# BD0005.net
KiCad netlist of a schematic drawn in EAGLE
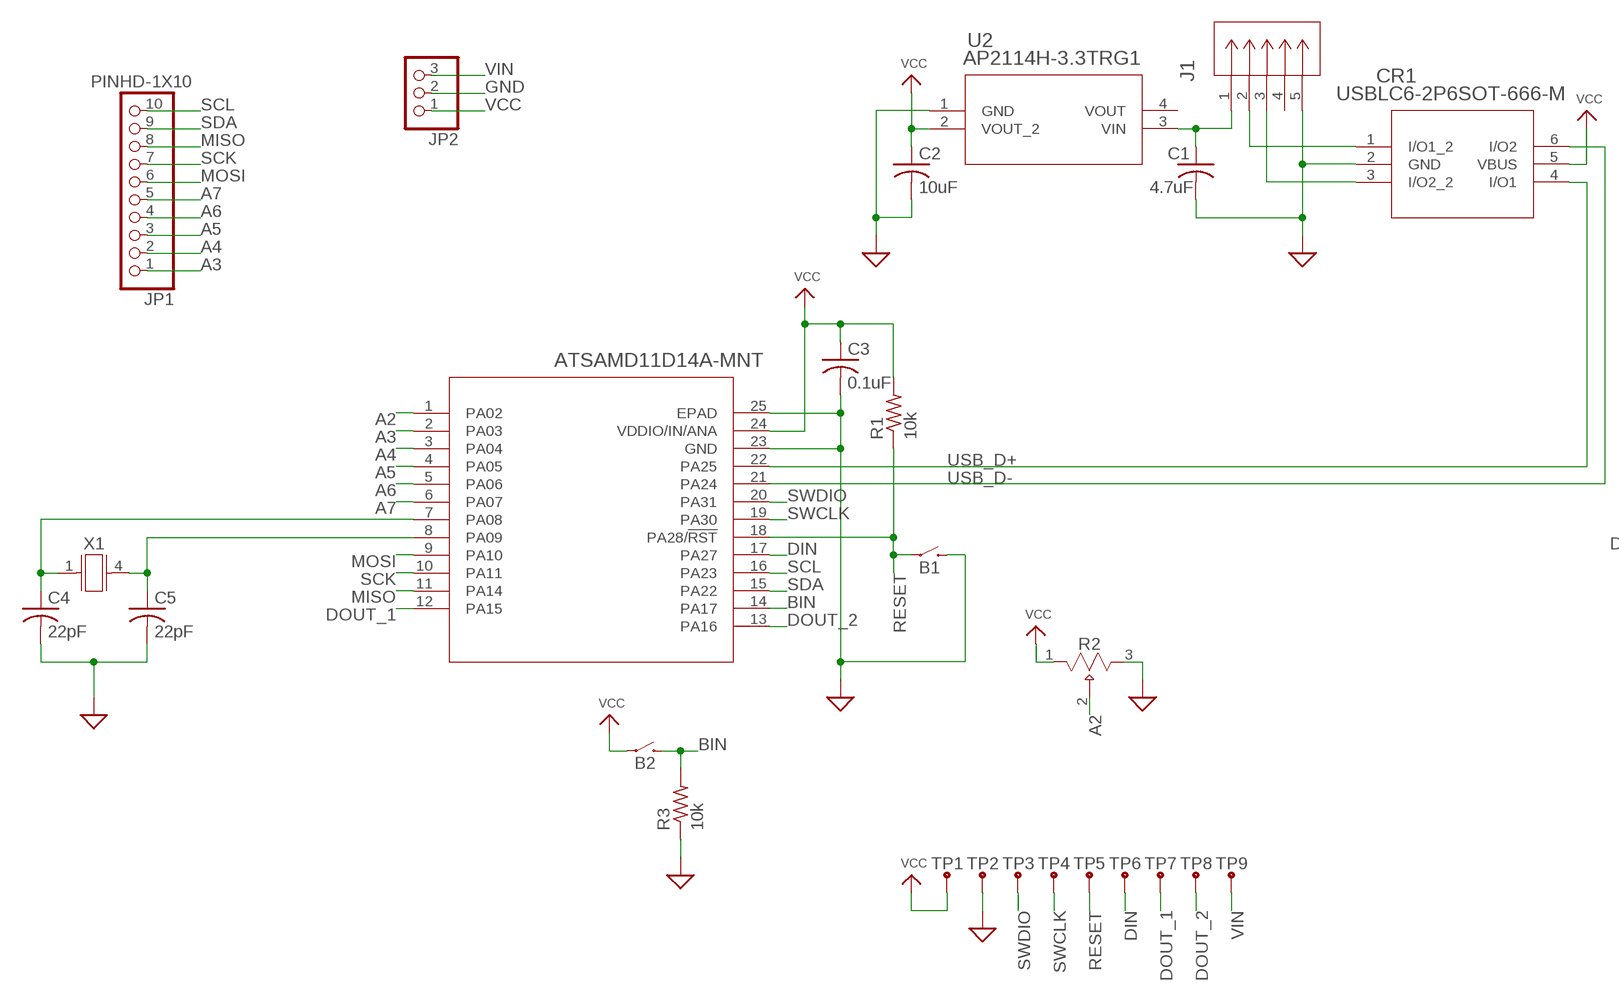
[diagram p0: schematic, sheet 1, part 1 of 2]
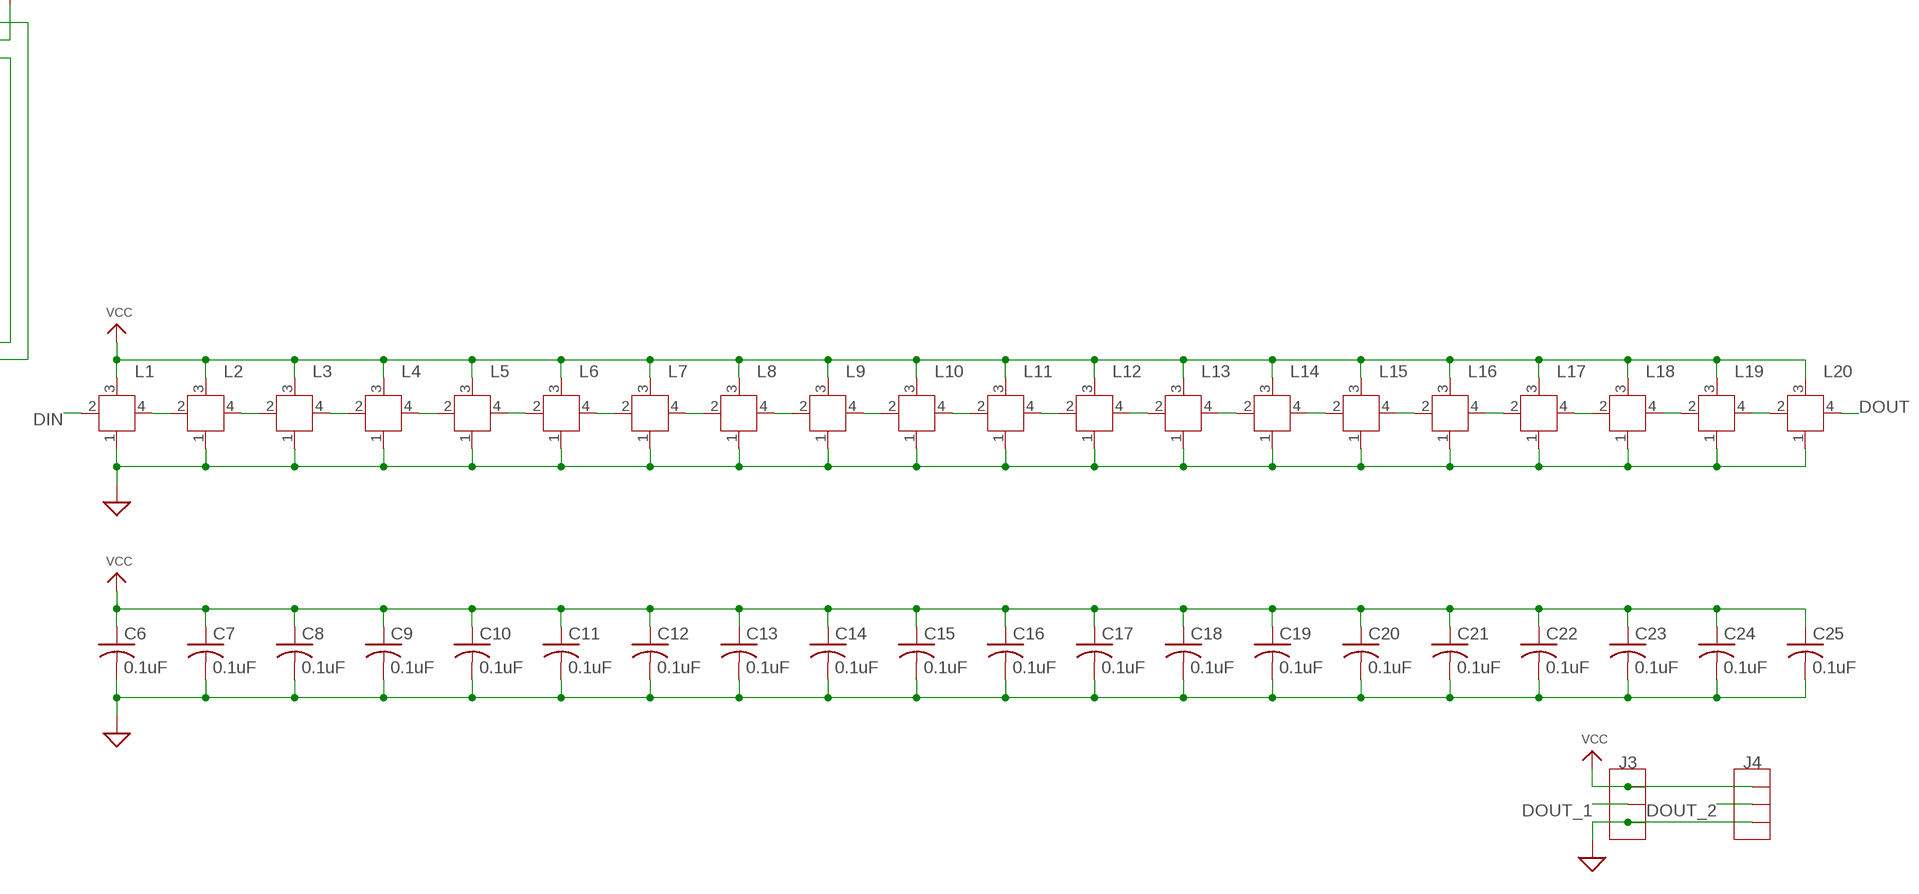
[diagram p1: schematic, sheet 1, part 2 of 2]

(export (version "E")
  (design (tool "Eeschema 10.0.6"))
  (components
    (comp (ref "B1")
      (value "EVQ-P7A01P")
      (footprint "eagle-import:4-SMD_BUTTON")
      (libsource (lib "eagle-import") (part "EVQ-P7A01P"))
    )
    (comp (ref "B2")
      (value "EVQ-P7A01P")
      (footprint "eagle-import:4-SMD_BUTTON")
      (libsource (lib "eagle-import") (part "EVQ-P7A01P"))
    )
    (comp (ref "C1")
      (value "4.7uF")
      (footprint "eagle-import:C0805")
      (libsource (lib "eagle-import") (part "C-USC0805"))
    )
    (comp (ref "C2")
      (value "10uF")
      (footprint "eagle-import:C0805")
      (libsource (lib "eagle-import") (part "C-USC0805"))
    )
    (comp (ref "C3")
      (value "0.1uF")
      (footprint "eagle-import:C0402")
      (libsource (lib "eagle-import") (part "C-USC0402"))
    )
    (comp (ref "C4")
      (value "22pF")
      (footprint "eagle-import:C0402")
      (libsource (lib "eagle-import") (part "C-USC0402"))
    )
    (comp (ref "C5")
      (value "22pF")
      (footprint "eagle-import:C0402")
      (libsource (lib "eagle-import") (part "C-USC0402"))
    )
    (comp (ref "C6")
      (value "0.1uF")
      (footprint "eagle-import:C0402")
      (libsource (lib "eagle-import") (part "C-USC0402"))
    )
    (comp (ref "C7")
      (value "0.1uF")
      (footprint "eagle-import:C0402")
      (libsource (lib "eagle-import") (part "C-USC0402"))
    )
    (comp (ref "C8")
      (value "0.1uF")
      (footprint "eagle-import:C0402")
      (libsource (lib "eagle-import") (part "C-USC0402"))
    )
    (comp (ref "C9")
      (value "0.1uF")
      (footprint "eagle-import:C0402")
      (libsource (lib "eagle-import") (part "C-USC0402"))
    )
    (comp (ref "C10")
      (value "0.1uF")
      (footprint "eagle-import:C0402")
      (libsource (lib "eagle-import") (part "C-USC0402"))
    )
    (comp (ref "C11")
      (value "0.1uF")
      (footprint "eagle-import:C0402")
      (libsource (lib "eagle-import") (part "C-USC0402"))
    )
    (comp (ref "C12")
      (value "0.1uF")
      (footprint "eagle-import:C0402")
      (libsource (lib "eagle-import") (part "C-USC0402"))
    )
    (comp (ref "C13")
      (value "0.1uF")
      (footprint "eagle-import:C0402")
      (libsource (lib "eagle-import") (part "C-USC0402"))
    )
    (comp (ref "C14")
      (value "0.1uF")
      (footprint "eagle-import:C0402")
      (libsource (lib "eagle-import") (part "C-USC0402"))
    )
    (comp (ref "C15")
      (value "0.1uF")
      (footprint "eagle-import:C0402")
      (libsource (lib "eagle-import") (part "C-USC0402"))
    )
    (comp (ref "C16")
      (value "0.1uF")
      (footprint "eagle-import:C0402")
      (libsource (lib "eagle-import") (part "C-USC0402"))
    )
    (comp (ref "C17")
      (value "0.1uF")
      (footprint "eagle-import:C0402")
      (libsource (lib "eagle-import") (part "C-USC0402"))
    )
    (comp (ref "C18")
      (value "0.1uF")
      (footprint "eagle-import:C0402")
      (libsource (lib "eagle-import") (part "C-USC0402"))
    )
    (comp (ref "C19")
      (value "0.1uF")
      (footprint "eagle-import:C0402")
      (libsource (lib "eagle-import") (part "C-USC0402"))
    )
    (comp (ref "C20")
      (value "0.1uF")
      (footprint "eagle-import:C0402")
      (libsource (lib "eagle-import") (part "C-USC0402"))
    )
    (comp (ref "C21")
      (value "0.1uF")
      (footprint "eagle-import:C0402")
      (libsource (lib "eagle-import") (part "C-USC0402"))
    )
    (comp (ref "C22")
      (value "0.1uF")
      (footprint "eagle-import:C0402")
      (libsource (lib "eagle-import") (part "C-USC0402"))
    )
    (comp (ref "C23")
      (value "0.1uF")
      (footprint "eagle-import:C0402")
      (libsource (lib "eagle-import") (part "C-USC0402"))
    )
    (comp (ref "C24")
      (value "0.1uF")
      (footprint "eagle-import:C0402")
      (libsource (lib "eagle-import") (part "C-USC0402"))
    )
    (comp (ref "C25")
      (value "0.1uF")
      (footprint "eagle-import:C0402")
      (libsource (lib "eagle-import") (part "C-USC0402"))
    )
    (comp (ref "CR1")
      (value "USBLC6-2P6SOT-666-M")
      (footprint "eagle-import:SOT-666-M")
      (fields (field (name "MANUFACTURER_PART_NUMBER") "USBLC6-2P6"))
      (libsource (lib "eagle-import") (part "USBLC6-2P6SOT-666-M"))
    )
    (comp (ref "J1")
      (value "1050171001")
      (footprint "eagle-import:CON00679_5")
      (fields (field (name "COPYRIGHT") "Copyright (C) 2016 Accelerated Designs. All rights reserved"))
      (libsource (lib "eagle-import") (part "1050171001"))
    )
    (comp (ref "J3")
      (value "HEADER_1X3FEMALE")
      (footprint "eagle-import:F3SMD")
      (libsource (lib "eagle-import") (part "HEADER_1X3FEMALE"))
    )
    (comp (ref "J4")
      (value "HEADER_1X3FEMALE")
      (footprint "eagle-import:F3SMD")
      (libsource (lib "eagle-import") (part "HEADER_1X3FEMALE"))
    )
    (comp (ref "JP1")
      (value "PINHD-1X10")
      (footprint "eagle-import:1X10-BIG")
      (libsource (lib "eagle-import") (part "PINHD-1X10"))
    )
    (comp (ref "JP2")
      (value "PINHD-1X3")
      (footprint "eagle-import:1X03")
      (libsource (lib "eagle-import") (part "PINHD-1X3"))
    )
    (comp (ref "L1")
      (value "WS2812B")
      (footprint "eagle-import:SK6812")
      (libsource (lib "eagle-import") (part "WS2812B"))
    )
    (comp (ref "L2")
      (value "WS2812B")
      (footprint "eagle-import:SK6812")
      (libsource (lib "eagle-import") (part "WS2812B"))
    )
    (comp (ref "L3")
      (value "WS2812B")
      (footprint "eagle-import:SK6812")
      (libsource (lib "eagle-import") (part "WS2812B"))
    )
    (comp (ref "L4")
      (value "WS2812B")
      (footprint "eagle-import:SK6812")
      (libsource (lib "eagle-import") (part "WS2812B"))
    )
    (comp (ref "L5")
      (value "WS2812B")
      (footprint "eagle-import:SK6812")
      (libsource (lib "eagle-import") (part "WS2812B"))
    )
    (comp (ref "L6")
      (value "WS2812B")
      (footprint "eagle-import:SK6812")
      (libsource (lib "eagle-import") (part "WS2812B"))
    )
    (comp (ref "L7")
      (value "WS2812B")
      (footprint "eagle-import:SK6812")
      (libsource (lib "eagle-import") (part "WS2812B"))
    )
    (comp (ref "L8")
      (value "WS2812B")
      (footprint "eagle-import:SK6812")
      (libsource (lib "eagle-import") (part "WS2812B"))
    )
    (comp (ref "L9")
      (value "WS2812B")
      (footprint "eagle-import:SK6812")
      (libsource (lib "eagle-import") (part "WS2812B"))
    )
    (comp (ref "L10")
      (value "WS2812B")
      (footprint "eagle-import:SK6812")
      (libsource (lib "eagle-import") (part "WS2812B"))
    )
    (comp (ref "L11")
      (value "WS2812B")
      (footprint "eagle-import:SK6812")
      (libsource (lib "eagle-import") (part "WS2812B"))
    )
    (comp (ref "L12")
      (value "WS2812B")
      (footprint "eagle-import:SK6812")
      (libsource (lib "eagle-import") (part "WS2812B"))
    )
    (comp (ref "L13")
      (value "WS2812B")
      (footprint "eagle-import:SK6812")
      (libsource (lib "eagle-import") (part "WS2812B"))
    )
    (comp (ref "L14")
      (value "WS2812B")
      (footprint "eagle-import:SK6812")
      (libsource (lib "eagle-import") (part "WS2812B"))
    )
    (comp (ref "L15")
      (value "WS2812B")
      (footprint "eagle-import:SK6812")
      (libsource (lib "eagle-import") (part "WS2812B"))
    )
    (comp (ref "L16")
      (value "WS2812B")
      (footprint "eagle-import:SK6812")
      (libsource (lib "eagle-import") (part "WS2812B"))
    )
    (comp (ref "L17")
      (value "WS2812B")
      (footprint "eagle-import:SK6812")
      (libsource (lib "eagle-import") (part "WS2812B"))
    )
    (comp (ref "L18")
      (value "WS2812B")
      (footprint "eagle-import:SK6812")
      (libsource (lib "eagle-import") (part "WS2812B"))
    )
    (comp (ref "L19")
      (value "WS2812B")
      (footprint "eagle-import:SK6812")
      (libsource (lib "eagle-import") (part "WS2812B"))
    )
    (comp (ref "L20")
      (value "WS2812B")
      (footprint "eagle-import:SK6812")
      (libsource (lib "eagle-import") (part "WS2812B"))
    )
    (comp (ref "R1")
      (value "10k")
      (footprint "eagle-import:R0402")
      (libsource (lib "eagle-import") (part "R-US_R0402"))
    )
    (comp (ref "R2")
      (value "3352T-1-104LF")
      (footprint "eagle-import:THUMBWHEEL")
      (libsource (lib "eagle-import") (part "3352T-1-104LF"))
    )
    (comp (ref "R3")
      (value "10k")
      (footprint "eagle-import:R0402")
      (libsource (lib "eagle-import") (part "R-US_R0402"))
    )
    (comp (ref "TP1")
      (value "VCC")
      (footprint "eagle-import:TEST_POINT")
      (libsource (lib "eagle-import") (part "TEST_POINT"))
    )
    (comp (ref "TP2")
      (value "GND")
      (footprint "eagle-import:TEST_POINT")
      (libsource (lib "eagle-import") (part "TEST_POINT"))
    )
    (comp (ref "TP3")
      (value "DIO")
      (footprint "eagle-import:TEST_POINT")
      (libsource (lib "eagle-import") (part "TEST_POINT"))
    )
    (comp (ref "TP4")
      (value "CLK")
      (footprint "eagle-import:TEST_POINT")
      (libsource (lib "eagle-import") (part "TEST_POINT"))
    )
    (comp (ref "TP5")
      (value "RST")
      (footprint "eagle-import:TEST_POINT")
      (libsource (lib "eagle-import") (part "TEST_POINT"))
    )
    (comp (ref "TP6")
      (value "DIN")
      (footprint "eagle-import:TEST_POINT")
      (libsource (lib "eagle-import") (part "TEST_POINT"))
    )
    (comp (ref "TP7")
      (value "DO1")
      (footprint "eagle-import:TEST_POINT")
      (libsource (lib "eagle-import") (part "TEST_POINT"))
    )
    (comp (ref "TP8")
      (value "DO2")
      (footprint "eagle-import:TEST_POINT")
      (libsource (lib "eagle-import") (part "TEST_POINT"))
    )
    (comp (ref "TP9")
      (value "VIN")
      (footprint "eagle-import:TEST_POINT")
      (libsource (lib "eagle-import") (part "TEST_POINT"))
    )
    (comp (ref "U1")
      (value "ATSAMD11D14A-MNT")
      (footprint "eagle-import:QFN24_4X4MC")
      (fields (field (name "COPYRIGHT") "Copyright (C) 2018 Accelerated Designs. All rights reserved"))
      (libsource (lib "eagle-import") (part "ATSAMD11D14A-MNT"))
    )
    (comp (ref "U2")
      (value "AP2114H-3.3TRG1")
      (footprint "eagle-import:SOT-223")
      (libsource (lib "eagle-import") (part "AP2114H-3.3TRG1"))
    )
    (comp (ref "X1")
      (value "MC-146-32.7680JKA-A0:ROHS")
      (footprint "eagle-import:4-SMD_FLAT_LEADS")
      (libsource (lib "eagle-import") (part "MC-146-32.7680JKA-A0{colon}ROHS"))
    )
  )
  (nets
    (net (code "1") (name "/A2") (class "Default")
      (node (ref "R2") (pin "2") (pinfunction "P$2_2") (pintype "bidirectional"))
      (node (ref "U1") (pin "1") (pinfunction "PA02_1") (pintype "bidirectional"))
    )
    (net (code "2") (name "/A3") (class "Default")
      (node (ref "JP1") (pin "1") (pinfunction "1_1") (pintype "passive"))
      (node (ref "U1") (pin "2") (pinfunction "PA03_2") (pintype "bidirectional"))
    )
    (net (code "3") (name "/A4") (class "Default")
      (node (ref "JP1") (pin "2") (pinfunction "2_2") (pintype "passive"))
      (node (ref "U1") (pin "3") (pinfunction "PA04_3") (pintype "bidirectional"))
    )
    (net (code "4") (name "/A5") (class "Default")
      (node (ref "JP1") (pin "3") (pinfunction "3_3") (pintype "passive"))
      (node (ref "U1") (pin "4") (pinfunction "PA05_4") (pintype "bidirectional"))
    )
    (net (code "5") (name "/A6") (class "Default")
      (node (ref "JP1") (pin "4") (pinfunction "4_4") (pintype "passive"))
      (node (ref "U1") (pin "5") (pinfunction "PA06_5") (pintype "bidirectional"))
    )
    (net (code "6") (name "/A7") (class "Default")
      (node (ref "JP1") (pin "5") (pinfunction "5_5") (pintype "passive"))
      (node (ref "U1") (pin "6") (pinfunction "PA07_6") (pintype "bidirectional"))
    )
    (net (code "7") (name "/BIN") (class "Default")
      (node (ref "B2") (pin "2A") (pinfunction "P$2_2A") (pintype "bidirectional"))
      (node (ref "B2") (pin "2B") (pinfunction "P$2_2B") (pintype "bidirectional"))
      (node (ref "R3") (pin "2") (pinfunction "2_2") (pintype "passive"))
      (node (ref "U1") (pin "14") (pinfunction "PA17_14") (pintype "bidirectional"))
    )
    (net (code "8") (name "/DIN") (class "Default")
      (node (ref "L1") (pin "2") (pinfunction "DIN_2") (pintype "bidirectional"))
      (node (ref "TP6") (pin "P$1") (pinfunction "P$1_P$1") (pintype "input"))
      (node (ref "U1") (pin "17") (pinfunction "PA27_17") (pintype "bidirectional"))
    )
    (net (code "9") (name "/DOUT") (class "Default")
      (node (ref "L20") (pin "4") (pinfunction "DOUT_4") (pintype "bidirectional"))
    )
    (net (code "10") (name "/DOUT_1") (class "Default")
      (node (ref "J3") (pin "2A") (pinfunction "P$2_2A") (pintype "bidirectional"))
      (node (ref "J3") (pin "2B") (pinfunction "P$2_2B") (pintype "bidirectional"))
      (node (ref "TP7") (pin "P$1") (pinfunction "P$1_P$1") (pintype "input"))
      (node (ref "U1") (pin "12") (pinfunction "PA15_12") (pintype "bidirectional"))
    )
    (net (code "11") (name "/DOUT_2") (class "Default")
      (node (ref "J4") (pin "2A") (pinfunction "P$2_2A") (pintype "bidirectional"))
      (node (ref "J4") (pin "2B") (pinfunction "P$2_2B") (pintype "bidirectional"))
      (node (ref "TP8") (pin "P$1") (pinfunction "P$1_P$1") (pintype "input"))
      (node (ref "U1") (pin "13") (pinfunction "PA16_13") (pintype "bidirectional"))
    )
    (net (code "12") (name "/MISO") (class "Default")
      (node (ref "JP1") (pin "8") (pinfunction "8_8") (pintype "passive"))
      (node (ref "U1") (pin "11") (pinfunction "PA14_11") (pintype "bidirectional"))
    )
    (net (code "13") (name "/MOSI") (class "Default")
      (node (ref "JP1") (pin "6") (pinfunction "6_6") (pintype "passive"))
      (node (ref "U1") (pin "9") (pinfunction "PA10_9") (pintype "bidirectional"))
    )
    (net (code "14") (name "/RESET") (class "Default")
      (node (ref "B1") (pin "1A") (pinfunction "P$1_1A") (pintype "bidirectional"))
      (node (ref "B1") (pin "1B") (pinfunction "P$1_1B") (pintype "bidirectional"))
      (node (ref "R1") (pin "1") (pinfunction "1_1") (pintype "passive"))
      (node (ref "TP5") (pin "P$1") (pinfunction "P$1_P$1") (pintype "input"))
      (node (ref "U1") (pin "18") (pinfunction "PA28/~{RST}_18") (pintype "bidirectional"))
    )
    (net (code "15") (name "/SCK") (class "Default")
      (node (ref "JP1") (pin "7") (pinfunction "7_7") (pintype "passive"))
      (node (ref "U1") (pin "10") (pinfunction "PA11_10") (pintype "bidirectional"))
    )
    (net (code "16") (name "/SCL") (class "Default")
      (node (ref "JP1") (pin "10") (pinfunction "10_10") (pintype "passive"))
      (node (ref "U1") (pin "16") (pinfunction "PA23_16") (pintype "bidirectional"))
    )
    (net (code "17") (name "/SDA") (class "Default")
      (node (ref "JP1") (pin "9") (pinfunction "9_9") (pintype "passive"))
      (node (ref "U1") (pin "15") (pinfunction "PA22_15") (pintype "bidirectional"))
    )
    (net (code "18") (name "/SWCLK") (class "Default")
      (node (ref "TP4") (pin "P$1") (pinfunction "P$1_P$1") (pintype "input"))
      (node (ref "U1") (pin "19") (pinfunction "PA30_19") (pintype "bidirectional"))
    )
    (net (code "19") (name "/SWDIO") (class "Default")
      (node (ref "TP3") (pin "P$1") (pinfunction "P$1_P$1") (pintype "input"))
      (node (ref "U1") (pin "20") (pinfunction "PA31_20") (pintype "bidirectional"))
    )
    (net (code "20") (name "/USB_D+") (class "Default")
      (node (ref "CR1") (pin "4") (pinfunction "I/O1_4") (pintype "bidirectional"))
      (node (ref "U1") (pin "22") (pinfunction "PA25_22") (pintype "bidirectional"))
    )
    (net (code "21") (name "/USB_D-") (class "Default")
      (node (ref "CR1") (pin "6") (pinfunction "I/O2_6") (pintype "bidirectional"))
      (node (ref "U1") (pin "21") (pinfunction "PA24_21") (pintype "bidirectional"))
    )
    (net (code "22") (name "/VIN") (class "Default")
      (node (ref "C1") (pin "1") (pinfunction "1_1") (pintype "passive"))
      (node (ref "J1") (pin "1") (pinfunction "1_1") (pintype "passive"))
      (node (ref "JP2") (pin "3") (pinfunction "3_3") (pintype "passive"))
      (node (ref "TP9") (pin "P$1") (pinfunction "P$1_P$1") (pintype "input"))
      (node (ref "U2") (pin "3") (pinfunction "VIN_3") (pintype "input"))
    )
    (net (code "23") (name "Net-(CR1-I{slash}O1_2)") (class "Default")
      (node (ref "CR1") (pin "1") (pinfunction "I/O1_2_1") (pintype "bidirectional"))
      (node (ref "J1") (pin "2") (pinfunction "2_2") (pintype "passive"))
    )
    (net (code "24") (name "Net-(CR1-I{slash}O2_2)") (class "Default")
      (node (ref "CR1") (pin "3") (pinfunction "I/O2_2_3") (pintype "bidirectional"))
      (node (ref "J1") (pin "3") (pinfunction "3_3") (pintype "passive"))
    )
    (net (code "25") (name "Net-(L1-DOUT)") (class "Default")
      (node (ref "L1") (pin "4") (pinfunction "DOUT_4") (pintype "bidirectional"))
      (node (ref "L2") (pin "2") (pinfunction "DIN_2") (pintype "bidirectional"))
    )
    (net (code "26") (name "Net-(L2-DOUT)") (class "Default")
      (node (ref "L2") (pin "4") (pinfunction "DOUT_4") (pintype "bidirectional"))
      (node (ref "L3") (pin "2") (pinfunction "DIN_2") (pintype "bidirectional"))
    )
    (net (code "27") (name "Net-(L3-DOUT)") (class "Default")
      (node (ref "L3") (pin "4") (pinfunction "DOUT_4") (pintype "bidirectional"))
      (node (ref "L4") (pin "2") (pinfunction "DIN_2") (pintype "bidirectional"))
    )
    (net (code "28") (name "Net-(L4-DOUT)") (class "Default")
      (node (ref "L4") (pin "4") (pinfunction "DOUT_4") (pintype "bidirectional"))
      (node (ref "L5") (pin "2") (pinfunction "DIN_2") (pintype "bidirectional"))
    )
    (net (code "29") (name "Net-(L5-DOUT)") (class "Default")
      (node (ref "L5") (pin "4") (pinfunction "DOUT_4") (pintype "bidirectional"))
      (node (ref "L6") (pin "2") (pinfunction "DIN_2") (pintype "bidirectional"))
    )
    (net (code "30") (name "Net-(L6-DOUT)") (class "Default")
      (node (ref "L6") (pin "4") (pinfunction "DOUT_4") (pintype "bidirectional"))
      (node (ref "L7") (pin "2") (pinfunction "DIN_2") (pintype "bidirectional"))
    )
    (net (code "31") (name "Net-(L7-DOUT)") (class "Default")
      (node (ref "L7") (pin "4") (pinfunction "DOUT_4") (pintype "bidirectional"))
      (node (ref "L8") (pin "2") (pinfunction "DIN_2") (pintype "bidirectional"))
    )
    (net (code "32") (name "Net-(L8-DOUT)") (class "Default")
      (node (ref "L8") (pin "4") (pinfunction "DOUT_4") (pintype "bidirectional"))
      (node (ref "L9") (pin "2") (pinfunction "DIN_2") (pintype "bidirectional"))
    )
    (net (code "33") (name "Net-(L10-DIN)") (class "Default")
      (node (ref "L10") (pin "2") (pinfunction "DIN_2") (pintype "bidirectional"))
      (node (ref "L9") (pin "4") (pinfunction "DOUT_4") (pintype "bidirectional"))
    )
    (net (code "34") (name "Net-(L10-DOUT)") (class "Default")
      (node (ref "L10") (pin "4") (pinfunction "DOUT_4") (pintype "bidirectional"))
      (node (ref "L11") (pin "2") (pinfunction "DIN_2") (pintype "bidirectional"))
    )
    (net (code "35") (name "Net-(L11-DOUT)") (class "Default")
      (node (ref "L11") (pin "4") (pinfunction "DOUT_4") (pintype "bidirectional"))
      (node (ref "L12") (pin "2") (pinfunction "DIN_2") (pintype "bidirectional"))
    )
    (net (code "36") (name "Net-(L12-DOUT)") (class "Default")
      (node (ref "L12") (pin "4") (pinfunction "DOUT_4") (pintype "bidirectional"))
      (node (ref "L13") (pin "2") (pinfunction "DIN_2") (pintype "bidirectional"))
    )
    (net (code "37") (name "Net-(L13-DOUT)") (class "Default")
      (node (ref "L13") (pin "4") (pinfunction "DOUT_4") (pintype "bidirectional"))
      (node (ref "L14") (pin "2") (pinfunction "DIN_2") (pintype "bidirectional"))
    )
    (net (code "38") (name "Net-(L14-DOUT)") (class "Default")
      (node (ref "L14") (pin "4") (pinfunction "DOUT_4") (pintype "bidirectional"))
      (node (ref "L15") (pin "2") (pinfunction "DIN_2") (pintype "bidirectional"))
    )
    (net (code "39") (name "Net-(L15-DOUT)") (class "Default")
      (node (ref "L15") (pin "4") (pinfunction "DOUT_4") (pintype "bidirectional"))
      (node (ref "L16") (pin "2") (pinfunction "DIN_2") (pintype "bidirectional"))
    )
    (net (code "40") (name "Net-(L16-DOUT)") (class "Default")
      (node (ref "L16") (pin "4") (pinfunction "DOUT_4") (pintype "bidirectional"))
      (node (ref "L17") (pin "2") (pinfunction "DIN_2") (pintype "bidirectional"))
    )
    (net (code "41") (name "Net-(L17-DOUT)") (class "Default")
      (node (ref "L17") (pin "4") (pinfunction "DOUT_4") (pintype "bidirectional"))
      (node (ref "L18") (pin "2") (pinfunction "DIN_2") (pintype "bidirectional"))
    )
    (net (code "42") (name "Net-(L18-DOUT)") (class "Default")
      (node (ref "L18") (pin "4") (pinfunction "DOUT_4") (pintype "bidirectional"))
      (node (ref "L19") (pin "2") (pinfunction "DIN_2") (pintype "bidirectional"))
    )
    (net (code "43") (name "Net-(L19-DOUT)") (class "Default")
      (node (ref "L19") (pin "4") (pinfunction "DOUT_4") (pintype "bidirectional"))
      (node (ref "L20") (pin "2") (pinfunction "DIN_2") (pintype "bidirectional"))
    )
    (net (code "44") (name "Net-(U1-PA08)") (class "Default")
      (node (ref "C4") (pin "1") (pinfunction "1_1") (pintype "passive"))
      (node (ref "U1") (pin "7") (pinfunction "PA08_7") (pintype "bidirectional"))
      (node (ref "X1") (pin "1") (pinfunction "P$1_1") (pintype "bidirectional"))
    )
    (net (code "45") (name "Net-(U1-PA09)") (class "Default")
      (node (ref "C5") (pin "1") (pinfunction "1_1") (pintype "passive"))
      (node (ref "U1") (pin "8") (pinfunction "PA09_8") (pintype "bidirectional"))
      (node (ref "X1") (pin "4") (pinfunction "P$2_4") (pintype "bidirectional"))
    )
    (net (code "46") (name "SUP") (class "Default")
      (node (ref "B1") (pin "2A") (pinfunction "P$2_2A") (pintype "bidirectional"))
      (node (ref "B1") (pin "2B") (pinfunction "P$2_2B") (pintype "bidirectional"))
      (node (ref "C1") (pin "2") (pinfunction "2_2") (pintype "passive"))
      (node (ref "C10") (pin "2") (pinfunction "2_2") (pintype "passive"))
      (node (ref "C11") (pin "2") (pinfunction "2_2") (pintype "passive"))
      (node (ref "C12") (pin "2") (pinfunction "2_2") (pintype "passive"))
      (node (ref "C13") (pin "2") (pinfunction "2_2") (pintype "passive"))
      (node (ref "C14") (pin "2") (pinfunction "2_2") (pintype "passive"))
      (node (ref "C15") (pin "2") (pinfunction "2_2") (pintype "passive"))
      (node (ref "C16") (pin "2") (pinfunction "2_2") (pintype "passive"))
      (node (ref "C17") (pin "2") (pinfunction "2_2") (pintype "passive"))
      (node (ref "C18") (pin "2") (pinfunction "2_2") (pintype "passive"))
      (node (ref "C19") (pin "2") (pinfunction "2_2") (pintype "passive"))
      (node (ref "C2") (pin "2") (pinfunction "2_2") (pintype "passive"))
      (node (ref "C20") (pin "2") (pinfunction "2_2") (pintype "passive"))
      (node (ref "C21") (pin "2") (pinfunction "2_2") (pintype "passive"))
      (node (ref "C22") (pin "2") (pinfunction "2_2") (pintype "passive"))
      (node (ref "C23") (pin "2") (pinfunction "2_2") (pintype "passive"))
      (node (ref "C24") (pin "2") (pinfunction "2_2") (pintype "passive"))
      (node (ref "C25") (pin "2") (pinfunction "2_2") (pintype "passive"))
      (node (ref "C3") (pin "2") (pinfunction "2_2") (pintype "passive"))
      (node (ref "C4") (pin "2") (pinfunction "2_2") (pintype "passive"))
      (node (ref "C5") (pin "2") (pinfunction "2_2") (pintype "passive"))
      (node (ref "C6") (pin "2") (pinfunction "2_2") (pintype "passive"))
      (node (ref "C7") (pin "2") (pinfunction "2_2") (pintype "passive"))
      (node (ref "C8") (pin "2") (pinfunction "2_2") (pintype "passive"))
      (node (ref "C9") (pin "2") (pinfunction "2_2") (pintype "passive"))
      (node (ref "CR1") (pin "2") (pinfunction "GND_2") (pintype "power_in"))
      (node (ref "J1") (pin "5") (pinfunction "5_5") (pintype "passive"))
      (node (ref "J3") (pin "3A") (pinfunction "P$3_3A") (pintype "bidirectional"))
      (node (ref "J3") (pin "3B") (pinfunction "P$3_3B") (pintype "bidirectional"))
      (node (ref "J4") (pin "3A") (pinfunction "P$3_3A") (pintype "bidirectional"))
      (node (ref "J4") (pin "3B") (pinfunction "P$3_3B") (pintype "bidirectional"))
      (node (ref "JP2") (pin "2") (pinfunction "2_2") (pintype "passive"))
      (node (ref "L1") (pin "1") (pinfunction "VSS_1") (pintype "bidirectional"))
      (node (ref "L10") (pin "1") (pinfunction "VSS_1") (pintype "bidirectional"))
      (node (ref "L11") (pin "1") (pinfunction "VSS_1") (pintype "bidirectional"))
      (node (ref "L12") (pin "1") (pinfunction "VSS_1") (pintype "bidirectional"))
      (node (ref "L13") (pin "1") (pinfunction "VSS_1") (pintype "bidirectional"))
      (node (ref "L14") (pin "1") (pinfunction "VSS_1") (pintype "bidirectional"))
      (node (ref "L15") (pin "1") (pinfunction "VSS_1") (pintype "bidirectional"))
      (node (ref "L16") (pin "1") (pinfunction "VSS_1") (pintype "bidirectional"))
      (node (ref "L17") (pin "1") (pinfunction "VSS_1") (pintype "bidirectional"))
      (node (ref "L18") (pin "1") (pinfunction "VSS_1") (pintype "bidirectional"))
      (node (ref "L19") (pin "1") (pinfunction "VSS_1") (pintype "bidirectional"))
      (node (ref "L2") (pin "1") (pinfunction "VSS_1") (pintype "bidirectional"))
      (node (ref "L20") (pin "1") (pinfunction "VSS_1") (pintype "bidirectional"))
      (node (ref "L3") (pin "1") (pinfunction "VSS_1") (pintype "bidirectional"))
      (node (ref "L4") (pin "1") (pinfunction "VSS_1") (pintype "bidirectional"))
      (node (ref "L5") (pin "1") (pinfunction "VSS_1") (pintype "bidirectional"))
      (node (ref "L6") (pin "1") (pinfunction "VSS_1") (pintype "bidirectional"))
      (node (ref "L7") (pin "1") (pinfunction "VSS_1") (pintype "bidirectional"))
      (node (ref "L8") (pin "1") (pinfunction "VSS_1") (pintype "bidirectional"))
      (node (ref "L9") (pin "1") (pinfunction "VSS_1") (pintype "bidirectional"))
      (node (ref "R2") (pin "3") (pinfunction "P$3_3") (pintype "bidirectional"))
      (node (ref "R3") (pin "1") (pinfunction "1_1") (pintype "passive"))
      (node (ref "TP2") (pin "P$1") (pinfunction "P$1_P$1") (pintype "input"))
      (node (ref "U1") (pin "23") (pinfunction "GND_23") (pintype "passive"))
      (node (ref "U1") (pin "25") (pinfunction "EPAD_25") (pintype "passive"))
      (node (ref "U2") (pin "1") (pinfunction "GND_1") (pintype "passive"))
    )
    (net (code "47") (name "VCC") (class "Default")
      (node (ref "B2") (pin "1A") (pinfunction "P$1_1A") (pintype "bidirectional"))
      (node (ref "B2") (pin "1B") (pinfunction "P$1_1B") (pintype "bidirectional"))
      (node (ref "C10") (pin "1") (pinfunction "1_1") (pintype "passive"))
      (node (ref "C11") (pin "1") (pinfunction "1_1") (pintype "passive"))
      (node (ref "C12") (pin "1") (pinfunction "1_1") (pintype "passive"))
      (node (ref "C13") (pin "1") (pinfunction "1_1") (pintype "passive"))
      (node (ref "C14") (pin "1") (pinfunction "1_1") (pintype "passive"))
      (node (ref "C15") (pin "1") (pinfunction "1_1") (pintype "passive"))
      (node (ref "C16") (pin "1") (pinfunction "1_1") (pintype "passive"))
      (node (ref "C17") (pin "1") (pinfunction "1_1") (pintype "passive"))
      (node (ref "C18") (pin "1") (pinfunction "1_1") (pintype "passive"))
      (node (ref "C19") (pin "1") (pinfunction "1_1") (pintype "passive"))
      (node (ref "C2") (pin "1") (pinfunction "1_1") (pintype "passive"))
      (node (ref "C20") (pin "1") (pinfunction "1_1") (pintype "passive"))
      (node (ref "C21") (pin "1") (pinfunction "1_1") (pintype "passive"))
      (node (ref "C22") (pin "1") (pinfunction "1_1") (pintype "passive"))
      (node (ref "C23") (pin "1") (pinfunction "1_1") (pintype "passive"))
      (node (ref "C24") (pin "1") (pinfunction "1_1") (pintype "passive"))
      (node (ref "C25") (pin "1") (pinfunction "1_1") (pintype "passive"))
      (node (ref "C3") (pin "1") (pinfunction "1_1") (pintype "passive"))
      (node (ref "C6") (pin "1") (pinfunction "1_1") (pintype "passive"))
      (node (ref "C7") (pin "1") (pinfunction "1_1") (pintype "passive"))
      (node (ref "C8") (pin "1") (pinfunction "1_1") (pintype "passive"))
      (node (ref "C9") (pin "1") (pinfunction "1_1") (pintype "passive"))
      (node (ref "CR1") (pin "5") (pinfunction "VBUS_5") (pintype "power_in"))
      (node (ref "J3") (pin "1A") (pinfunction "P$1_1A") (pintype "bidirectional"))
      (node (ref "J3") (pin "1B") (pinfunction "P$1_1B") (pintype "bidirectional"))
      (node (ref "J4") (pin "1A") (pinfunction "P$1_1A") (pintype "bidirectional"))
      (node (ref "J4") (pin "1B") (pinfunction "P$1_1B") (pintype "bidirectional"))
      (node (ref "JP2") (pin "1") (pinfunction "1_1") (pintype "passive"))
      (node (ref "L1") (pin "3") (pinfunction "VDD_3") (pintype "bidirectional"))
      (node (ref "L10") (pin "3") (pinfunction "VDD_3") (pintype "bidirectional"))
      (node (ref "L11") (pin "3") (pinfunction "VDD_3") (pintype "bidirectional"))
      (node (ref "L12") (pin "3") (pinfunction "VDD_3") (pintype "bidirectional"))
      (node (ref "L13") (pin "3") (pinfunction "VDD_3") (pintype "bidirectional"))
      (node (ref "L14") (pin "3") (pinfunction "VDD_3") (pintype "bidirectional"))
      (node (ref "L15") (pin "3") (pinfunction "VDD_3") (pintype "bidirectional"))
      (node (ref "L16") (pin "3") (pinfunction "VDD_3") (pintype "bidirectional"))
      (node (ref "L17") (pin "3") (pinfunction "VDD_3") (pintype "bidirectional"))
      (node (ref "L18") (pin "3") (pinfunction "VDD_3") (pintype "bidirectional"))
      (node (ref "L19") (pin "3") (pinfunction "VDD_3") (pintype "bidirectional"))
      (node (ref "L2") (pin "3") (pinfunction "VDD_3") (pintype "bidirectional"))
      (node (ref "L20") (pin "3") (pinfunction "VDD_3") (pintype "bidirectional"))
      (node (ref "L3") (pin "3") (pinfunction "VDD_3") (pintype "bidirectional"))
      (node (ref "L4") (pin "3") (pinfunction "VDD_3") (pintype "bidirectional"))
      (node (ref "L5") (pin "3") (pinfunction "VDD_3") (pintype "bidirectional"))
      (node (ref "L6") (pin "3") (pinfunction "VDD_3") (pintype "bidirectional"))
      (node (ref "L7") (pin "3") (pinfunction "VDD_3") (pintype "bidirectional"))
      (node (ref "L8") (pin "3") (pinfunction "VDD_3") (pintype "bidirectional"))
      (node (ref "L9") (pin "3") (pinfunction "VDD_3") (pintype "bidirectional"))
      (node (ref "R1") (pin "2") (pinfunction "2_2") (pintype "passive"))
      (node (ref "R2") (pin "1") (pinfunction "P$1_1") (pintype "bidirectional"))
      (node (ref "TP1") (pin "P$1") (pinfunction "P$1_P$1") (pintype "input"))
      (node (ref "U1") (pin "24") (pinfunction "VDDIO/IN/ANA_24") (pintype "power_in"))
      (node (ref "U2") (pin "2") (pinfunction "VOUT_2_2") (pintype "output"))
    )
    (net (code "48") (name "unconnected-(J1-Pad4)") (class "Default")
      (node (ref "J1") (pin "4") (pinfunction "4_4") (pintype "passive"))
    )
    (net (code "49") (name "unconnected-(U2-VOUT-Pad4)") (class "Default")
      (node (ref "U2") (pin "4") (pinfunction "VOUT_4") (pintype "output"))
    )
  )
)
